# SCH_ess_macropad_2026-09-29.net
KiCad netlist of a schematic drawn in EasyEDA
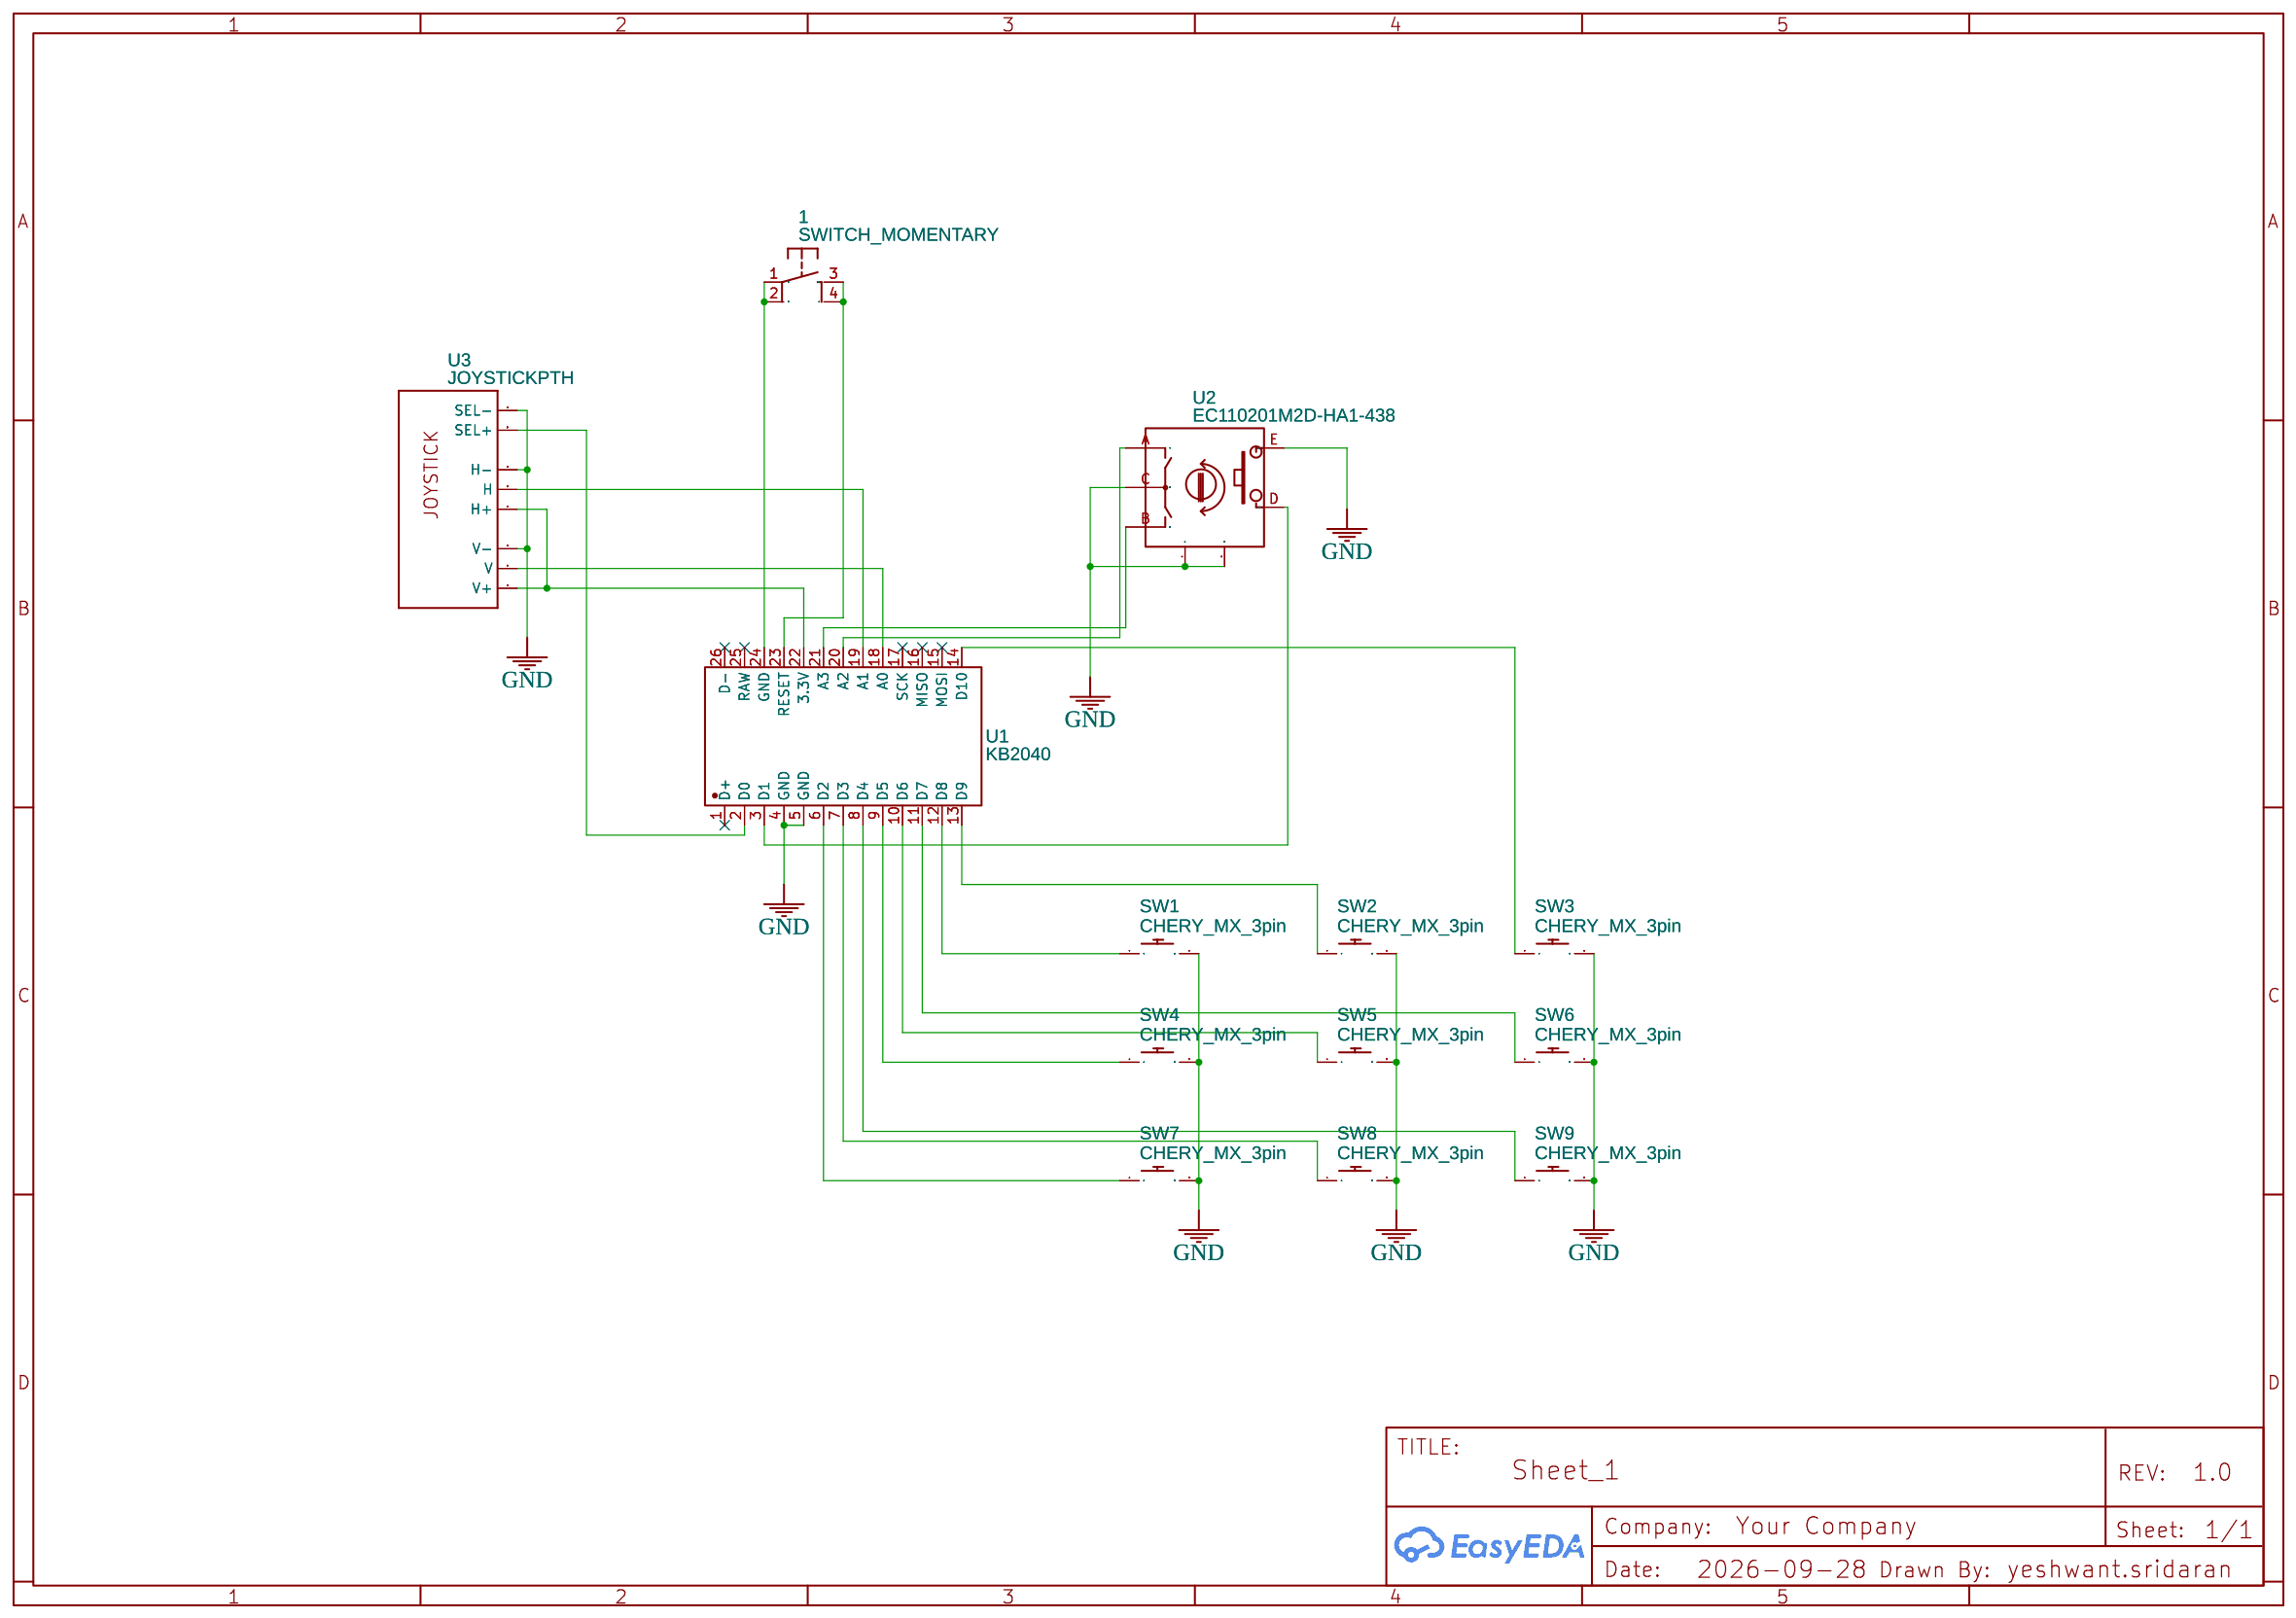
[diagram p0: schematic sheet]

(export (version "E")
  (design (tool "Eeschema 10.0.6"))
  (components
    (comp (ref "1") (value "SWITCH_MOMENTARY") (libsource (lib "") (part "SWITCH_MOMENTARY")))
    (comp (ref "SW1")
      (value "CHERY_MX_3pin")
      (fields (field (name "Manufacturer Part") "CHERY MX 3pin") (field (name "Manufacturer") "None"))
      (libsource (lib "") (part "CHERY_MX_3pin"))
    )
    (comp (ref "SW2")
      (value "CHERY_MX_3pin")
      (fields (field (name "Manufacturer Part") "CHERY MX 3pin") (field (name "Manufacturer") "None"))
      (libsource (lib "") (part "CHERY_MX_3pin"))
    )
    (comp (ref "SW3")
      (value "CHERY_MX_3pin")
      (fields (field (name "Manufacturer Part") "CHERY MX 3pin") (field (name "Manufacturer") "None"))
      (libsource (lib "") (part "CHERY_MX_3pin"))
    )
    (comp (ref "SW4")
      (value "CHERY_MX_3pin")
      (fields (field (name "Manufacturer Part") "CHERY MX 3pin") (field (name "Manufacturer") "None"))
      (libsource (lib "") (part "CHERY_MX_3pin"))
    )
    (comp (ref "SW5")
      (value "CHERY_MX_3pin")
      (fields (field (name "Manufacturer Part") "CHERY MX 3pin") (field (name "Manufacturer") "None"))
      (libsource (lib "") (part "CHERY_MX_3pin"))
    )
    (comp (ref "SW6")
      (value "CHERY_MX_3pin")
      (fields (field (name "Manufacturer Part") "CHERY MX 3pin") (field (name "Manufacturer") "None"))
      (libsource (lib "") (part "CHERY_MX_3pin"))
    )
    (comp (ref "SW7")
      (value "CHERY_MX_3pin")
      (fields (field (name "Manufacturer Part") "CHERY MX 3pin") (field (name "Manufacturer") "None"))
      (libsource (lib "") (part "CHERY_MX_3pin"))
    )
    (comp (ref "SW8")
      (value "CHERY_MX_3pin")
      (fields (field (name "Manufacturer Part") "CHERY MX 3pin") (field (name "Manufacturer") "None"))
      (libsource (lib "") (part "CHERY_MX_3pin"))
    )
    (comp (ref "SW9")
      (value "CHERY_MX_3pin")
      (fields (field (name "Manufacturer Part") "CHERY MX 3pin") (field (name "Manufacturer") "None"))
      (libsource (lib "") (part "CHERY_MX_3pin"))
    )
    (comp (ref "U1") (value "KB2040") (libsource (lib "") (part "KB2040")))
    (comp (ref "U2") (value "EC110201M2D-HA1-438") (libsource (lib "") (part "EC110201M2D-HA1-438")))
    (comp (ref "U3") (value "JOYSTICKPTH") (libsource (lib "") (part "JOYSTICKPTH")))
  )
  (nets
    (net (code "1") (name "GND") (class "Default")
      (node (ref "SW1") (pin "2") (pinfunction "2_2") (pintype "bidirectional"))
      (node (ref "SW2") (pin "2") (pinfunction "2_2") (pintype "bidirectional"))
      (node (ref "SW3") (pin "2") (pinfunction "2_2") (pintype "bidirectional"))
      (node (ref "SW4") (pin "2") (pinfunction "2_2") (pintype "bidirectional"))
      (node (ref "SW5") (pin "2") (pinfunction "2_2") (pintype "bidirectional"))
      (node (ref "SW6") (pin "2") (pinfunction "2_2") (pintype "bidirectional"))
      (node (ref "SW7") (pin "2") (pinfunction "2_2") (pintype "bidirectional"))
      (node (ref "SW8") (pin "2") (pinfunction "2_2") (pintype "bidirectional"))
      (node (ref "SW9") (pin "2") (pinfunction "2_2") (pintype "bidirectional"))
      (node (ref "U1") (pin "4") (pinfunction "GND_4") (pintype "unspecified"))
      (node (ref "U1") (pin "5") (pinfunction "GND_5") (pintype "unspecified"))
      (node (ref "U2") (pin "1") (pinfunction "1_1") (pintype "unspecified"))
      (node (ref "U2") (pin "2") (pinfunction "2_2") (pintype "unspecified"))
      (node (ref "U2") (pin "C") (pinfunction "C_C") (pintype "unspecified"))
      (node (ref "U2") (pin "E") (pinfunction "E_E") (pintype "unspecified"))
      (node (ref "U3") (pin "B2A") (pinfunction "SEL-_B2A") (pintype "unspecified"))
      (node (ref "U3") (pin "H3") (pinfunction "H-_H3") (pintype "unspecified"))
      (node (ref "U3") (pin "V3") (pinfunction "V-_V3") (pintype "unspecified"))
    )
    (net (code "2") (name "Net-(1-Pad1)") (class "Default")
      (node (ref "1") (pin "1") (pinfunction "1_1") (pintype "bidirectional"))
      (node (ref "1") (pin "2") (pinfunction "2_2") (pintype "bidirectional"))
      (node (ref "U1") (pin "24") (pinfunction "GND_24") (pintype "unspecified"))
    )
    (net (code "3") (name "Net-(U1-3.3V)") (class "Default")
      (node (ref "U1") (pin "22") (pinfunction "3.3V_22") (pintype "unspecified"))
      (node (ref "U3") (pin "H1") (pinfunction "H+_H1") (pintype "unspecified"))
      (node (ref "U3") (pin "V1") (pinfunction "V+_V1") (pintype "unspecified"))
    )
    (net (code "4") (name "Net-(U1-A0)") (class "Default")
      (node (ref "U1") (pin "18") (pinfunction "A0_18") (pintype "unspecified"))
      (node (ref "U3") (pin "V2") (pinfunction "V_V2") (pintype "unspecified"))
    )
    (net (code "5") (name "Net-(U1-A1)") (class "Default")
      (node (ref "U1") (pin "19") (pinfunction "A1_19") (pintype "unspecified"))
      (node (ref "U3") (pin "H2") (pinfunction "H_H2") (pintype "unspecified"))
    )
    (net (code "6") (name "Net-(U1-A2)") (class "Default")
      (node (ref "U1") (pin "20") (pinfunction "A2_20") (pintype "unspecified"))
      (node (ref "U2") (pin "A") (pinfunction "A_A") (pintype "unspecified"))
    )
    (net (code "7") (name "Net-(U1-A3)") (class "Default")
      (node (ref "U1") (pin "21") (pinfunction "A3_21") (pintype "unspecified"))
      (node (ref "U2") (pin "B") (pinfunction "B_B") (pintype "unspecified"))
    )
    (net (code "8") (name "Net-(U1-D0)") (class "Default")
      (node (ref "U1") (pin "2") (pinfunction "D0_2") (pintype "unspecified"))
      (node (ref "U3") (pin "B1A") (pinfunction "SEL+_B1A") (pintype "unspecified"))
    )
    (net (code "9") (name "Net-(U1-D1)") (class "Default")
      (node (ref "U1") (pin "3") (pinfunction "D1_3") (pintype "unspecified"))
      (node (ref "U2") (pin "D") (pinfunction "D_D") (pintype "unspecified"))
    )
    (net (code "10") (name "Net-(U1-D2)") (class "Default")
      (node (ref "SW7") (pin "1") (pinfunction "1_1") (pintype "bidirectional"))
      (node (ref "U1") (pin "6") (pinfunction "D2_6") (pintype "unspecified"))
    )
    (net (code "11") (name "Net-(U1-D3)") (class "Default")
      (node (ref "SW8") (pin "1") (pinfunction "1_1") (pintype "bidirectional"))
      (node (ref "U1") (pin "7") (pinfunction "D3_7") (pintype "unspecified"))
    )
    (net (code "12") (name "Net-(U1-D4)") (class "Default")
      (node (ref "SW9") (pin "1") (pinfunction "1_1") (pintype "bidirectional"))
      (node (ref "U1") (pin "8") (pinfunction "D4_8") (pintype "unspecified"))
    )
    (net (code "13") (name "Net-(U1-D5)") (class "Default")
      (node (ref "SW4") (pin "1") (pinfunction "1_1") (pintype "bidirectional"))
      (node (ref "U1") (pin "9") (pinfunction "D5_9") (pintype "unspecified"))
    )
    (net (code "14") (name "Net-(U1-D6)") (class "Default")
      (node (ref "SW5") (pin "1") (pinfunction "1_1") (pintype "bidirectional"))
      (node (ref "U1") (pin "10") (pinfunction "D6_10") (pintype "unspecified"))
    )
    (net (code "15") (name "Net-(U1-D7)") (class "Default")
      (node (ref "SW6") (pin "1") (pinfunction "1_1") (pintype "bidirectional"))
      (node (ref "U1") (pin "11") (pinfunction "D7_11") (pintype "unspecified"))
    )
    (net (code "16") (name "Net-(U1-D8)") (class "Default")
      (node (ref "SW1") (pin "1") (pinfunction "1_1") (pintype "bidirectional"))
      (node (ref "U1") (pin "12") (pinfunction "D8_12") (pintype "unspecified"))
    )
    (net (code "17") (name "Net-(U1-D9)") (class "Default")
      (node (ref "SW2") (pin "1") (pinfunction "1_1") (pintype "bidirectional"))
      (node (ref "U1") (pin "13") (pinfunction "D9_13") (pintype "unspecified"))
    )
    (net (code "18") (name "Net-(U1-D10)") (class "Default")
      (node (ref "SW3") (pin "1") (pinfunction "1_1") (pintype "bidirectional"))
      (node (ref "U1") (pin "14") (pinfunction "D10_14") (pintype "unspecified"))
    )
    (net (code "19") (name "Net-(U1-RESET)") (class "Default")
      (node (ref "1") (pin "3") (pinfunction "3_3") (pintype "bidirectional"))
      (node (ref "1") (pin "4") (pinfunction "4_4") (pintype "bidirectional"))
      (node (ref "U1") (pin "23") (pinfunction "RESET_23") (pintype "unspecified"))
    )
    (net (code "20") (name "unconnected-(U1-D+-Pad1)") (class "Default")
      (node (ref "U1") (pin "1") (pinfunction "D+_1") (pintype "unspecified+no_connect"))
    )
    (net (code "21") (name "unconnected-(U1-D--Pad26)") (class "Default")
      (node (ref "U1") (pin "26") (pinfunction "D-_26") (pintype "unspecified+no_connect"))
    )
    (net (code "22") (name "unconnected-(U1-MISO-Pad16)") (class "Default")
      (node (ref "U1") (pin "16") (pinfunction "MISO_16") (pintype "unspecified+no_connect"))
    )
    (net (code "23") (name "unconnected-(U1-MOSI-Pad15)") (class "Default")
      (node (ref "U1") (pin "15") (pinfunction "MOSI_15") (pintype "unspecified+no_connect"))
    )
    (net (code "24") (name "unconnected-(U1-RAW-Pad25)") (class "Default")
      (node (ref "U1") (pin "25") (pinfunction "RAW_25") (pintype "unspecified+no_connect"))
    )
    (net (code "25") (name "unconnected-(U1-SCK-Pad17)") (class "Default")
      (node (ref "U1") (pin "17") (pinfunction "SCK_17") (pintype "unspecified+no_connect"))
    )
  )
)
